# SCH_PHOENIX_-_PCB-2.net
KiCad netlist of a schematic drawn in EasyEDA
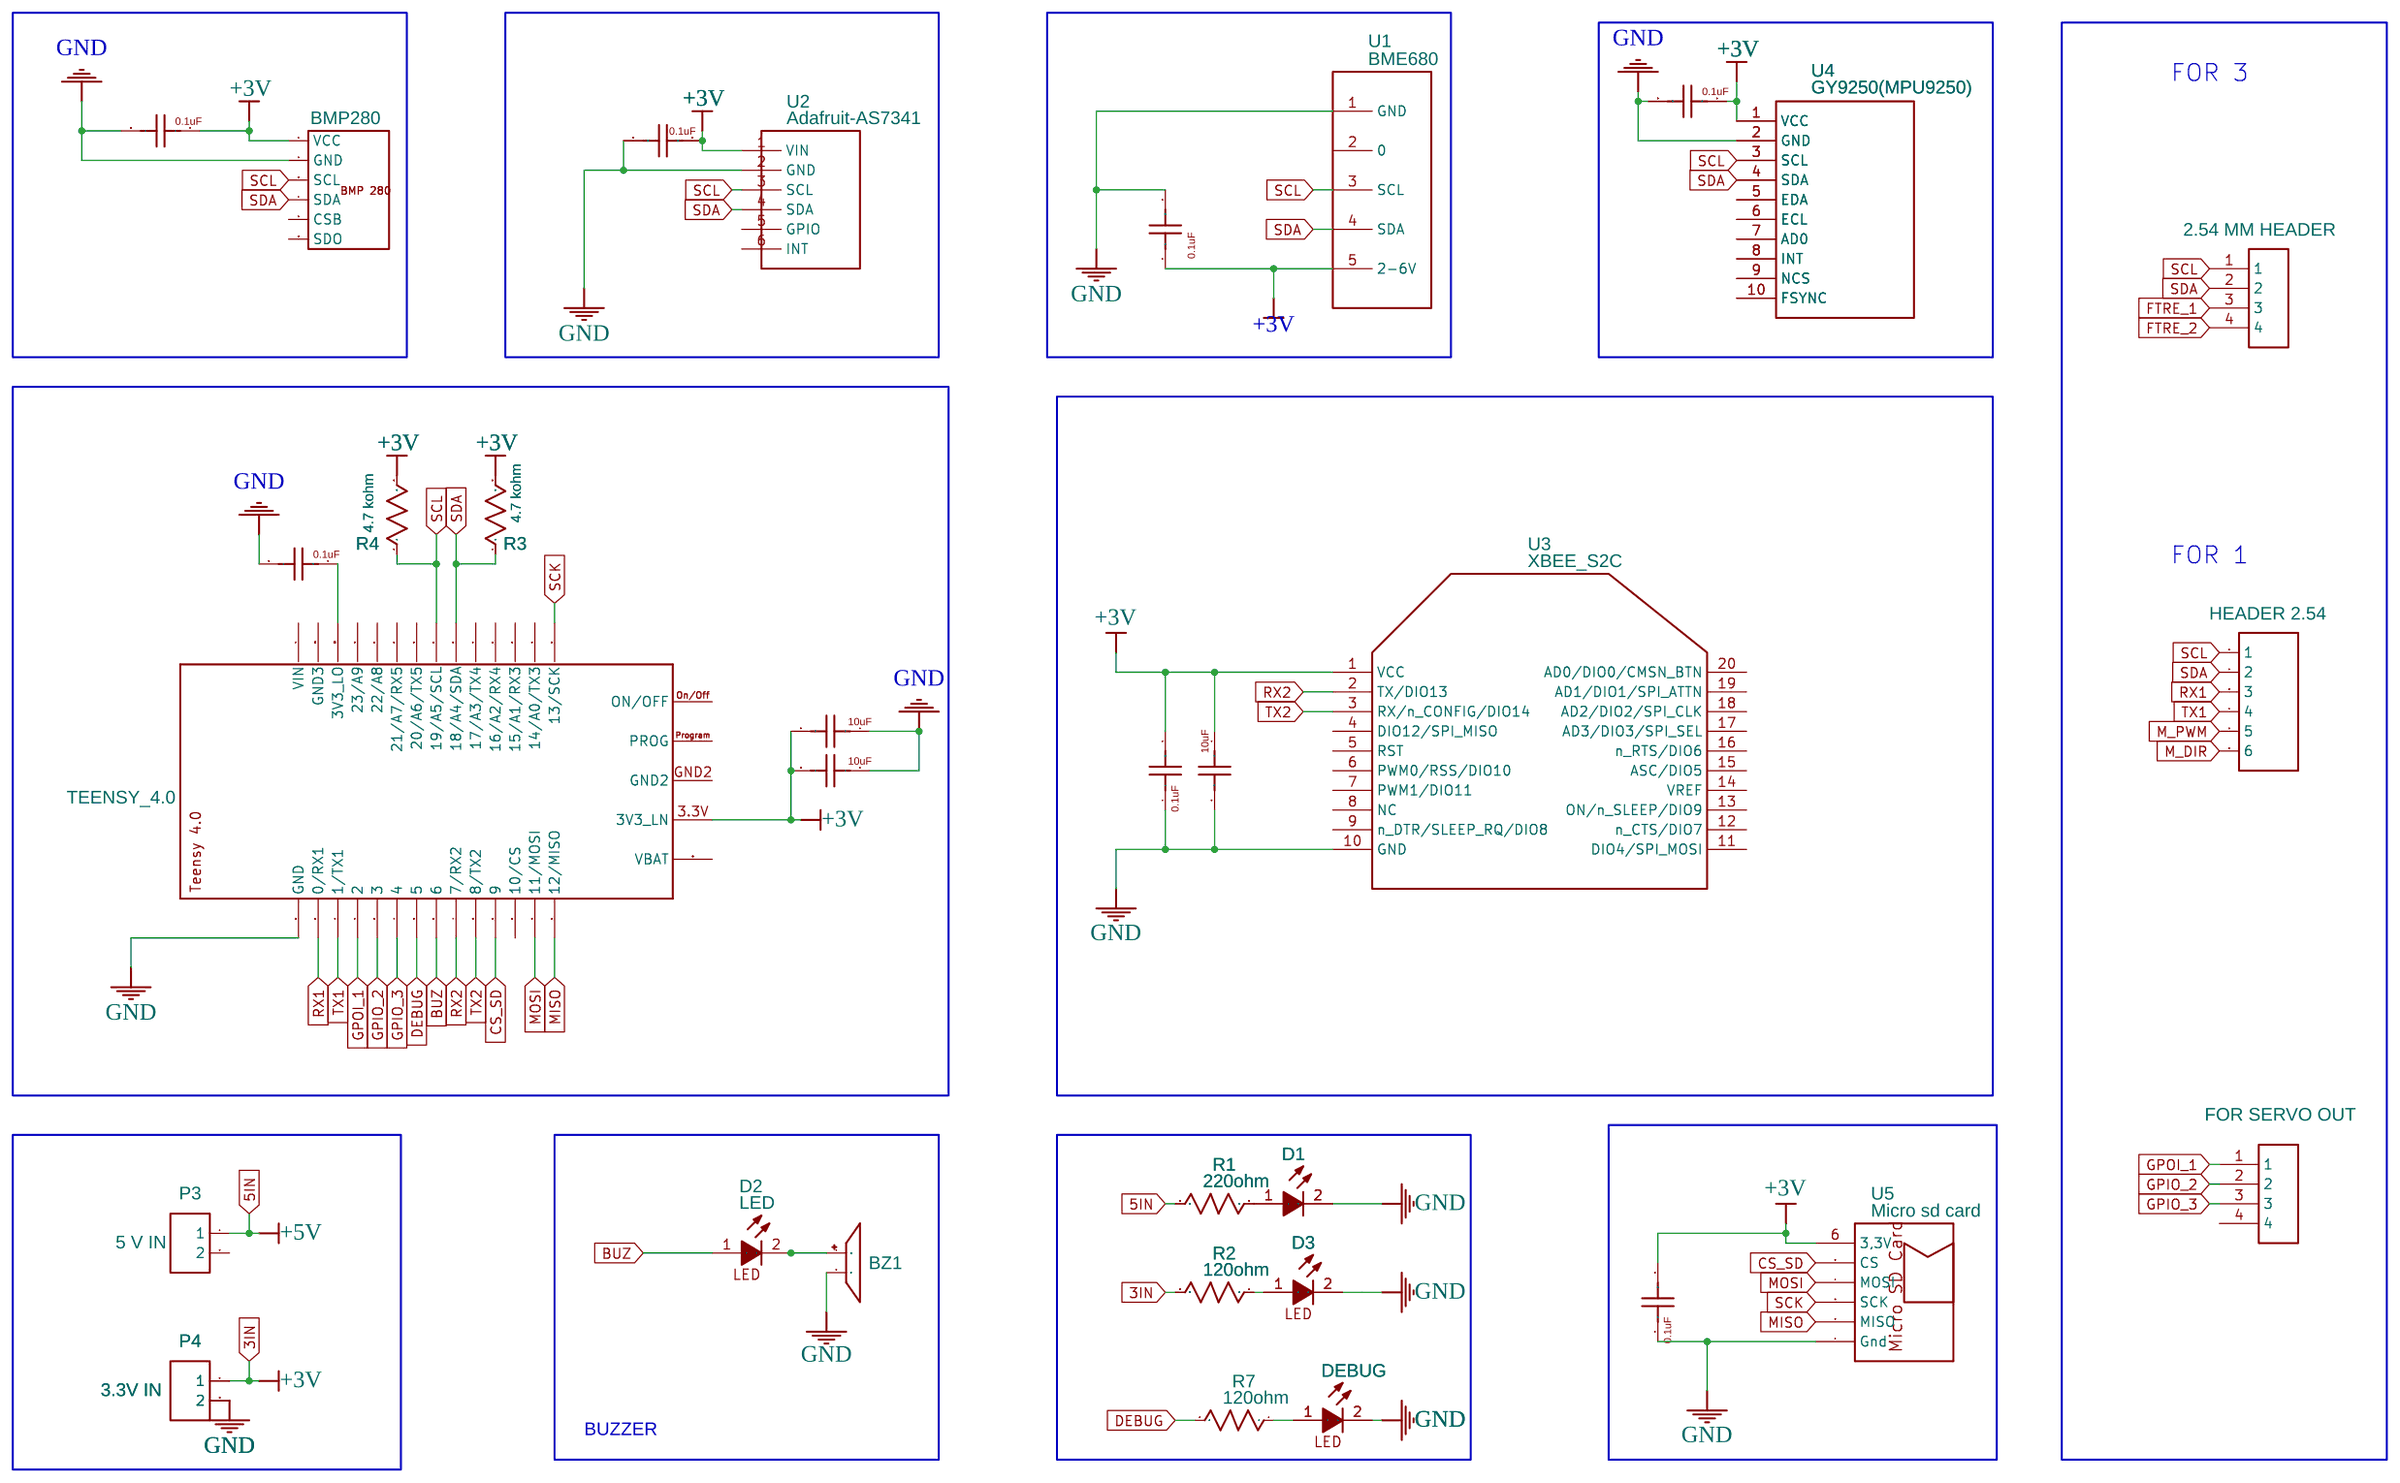
[diagram p0: schematic sheet]

(export (version "E")
  (design (tool "Eeschema 10.0.6"))
  (components
    (comp (ref "0") (value "TEENSY_4.0") (libsource (lib "") (part "TEENSY_4.0")))
    (comp (ref "BZ1") (value "Buzzer") (libsource (lib "") (part "Buzzer")))
    (comp (ref "C1") (value "22PF CERAMIC CAPACITOR") (libsource (lib "") (part "22PF CERAMIC CAPACITOR_1")))
    (comp (ref "C2") (value "22PF CERAMIC CAPACITOR") (libsource (lib "") (part "22PF CERAMIC CAPACITOR_1")))
    (comp (ref "C3") (value "22PF CERAMIC CAPACITOR") (libsource (lib "") (part "22PF CERAMIC CAPACITOR_6")))
    (comp (ref "C4") (value "22PF CERAMIC CAPACITOR") (libsource (lib "") (part "22PF CERAMIC CAPACITOR_3")))
    (comp (ref "C5") (value "22PF CERAMIC CAPACITOR") (libsource (lib "") (part "22PF CERAMIC CAPACITOR")))
    (comp (ref "C6") (value "22PF CERAMIC CAPACITOR") (libsource (lib "") (part "22PF CERAMIC CAPACITOR_3")))
    (comp (ref "C7") (value "22PF CERAMIC CAPACITOR") (libsource (lib "") (part "22PF CERAMIC CAPACITOR_4")))
    (comp (ref "C8") (value "22PF CERAMIC CAPACITOR") (libsource (lib "") (part "22PF CERAMIC CAPACITOR_5")))
    (comp (ref "C9") (value "22PF CERAMIC CAPACITOR") (libsource (lib "") (part "22PF CERAMIC CAPACITOR_2")))
    (comp (ref "C10") (value "22PF CERAMIC CAPACITOR") (libsource (lib "") (part "22PF CERAMIC CAPACITOR")))
    (comp (ref "D1")
      (value "LED")
      (fields (field (name "Manufacturer Part") "5600") (field (name "Manufacturer") "VccLite"))
      (libsource (lib "") (part "LED_1"))
    )
    (comp (ref "D2")
      (value "LED")
      (fields (field (name "Manufacturer Part") "5600") (field (name "Manufacturer") "VccLite"))
      (libsource (lib "") (part "LED"))
    )
    (comp (ref "D3")
      (value "LED")
      (fields (field (name "Manufacturer Part") "5600") (field (name "Manufacturer") "VccLite"))
      (libsource (lib "") (part "LED"))
    )
    (comp (ref "DEBUG")
      (value "LED")
      (fields (field (name "Manufacturer Part") "5600") (field (name "Manufacturer") "VccLite"))
      (libsource (lib "") (part "LED_2"))
    )
    (comp (ref "H1")
      (value "2.54 MM HEADER")
      (fields (field (name "Manufacturer Part") "2211S-04G") (field (name "Manufacturer") "MULTICOMP PRO"))
      (libsource (lib "") (part "B2B 2.54 MM HEADER"))
    )
    (comp (ref "H2")
      (value "FOR SERVO OUT")
      (fields (field (name "Manufacturer Part") "2211S-04G") (field (name "Manufacturer") "MULTICOMP PRO"))
      (libsource (lib "") (part "B2B 2.54 MM HEADER"))
    )
    (comp (ref "J1")
      (value "HEADER 2.54")
      (fields (field (name "Manufacturer Part") "2.54mm 1*20PHeader"))
      (libsource (lib "") (part "HEADER-MALE-2.54_1X6"))
    )
    (comp (ref "MOD1") (value "BMP280") (libsource (lib "") (part "BMP280")))
    (comp (ref "P3") (value "5 V IN") (libsource (lib "") (part "CONN-TH_2P-P5.00")))
    (comp (ref "P4") (value "3.3V IN") (libsource (lib "") (part "CONN-TH_2P-P5.00")))
    (comp (ref "R1") (value "220ohm") (libsource (lib "") (part "R_0603_US_1")))
    (comp (ref "R2") (value "120ohm") (libsource (lib "") (part "R_0603_US_1")))
    (comp (ref "R3") (value "4.7 kohm") (libsource (lib "") (part "R_0603_US")))
    (comp (ref "R4") (value "4.7 kohm") (libsource (lib "") (part "R_0603_US")))
    (comp (ref "R7") (value "120ohm") (libsource (lib "") (part "R_0603_US_1")))
    (comp (ref "U1") (value "BME680") (libsource (lib "") (part "BME680")))
    (comp (ref "U2") (value "Adafruit-AS7341") (libsource (lib "") (part "Adafruit-AS7341")))
    (comp (ref "U3")
      (value "XBEE_S2C")
      (fields
        (field (name "Manufacturer Part") "XBP24CZ7PITB003")
        (field (name "Manufacturer") "Digi International")
      )
      (libsource (lib "") (part "XBEE_S2C"))
    )
    (comp (ref "U4") (value "GY9250(MPU9250)") (libsource (lib "") (part "GY9250(MPU9250)")))
    (comp (ref "U5")
      (value "Micro sd card")
      (fields (field (name "Manufacturer Part") "Micro sd card module"))
      (libsource (lib "") (part "Micro sd card module"))
    )
  )
  (nets
    (net (code "1") (name "3IN") (class "Default")
      (node (ref "0") (pin "3.3V") (pinfunction "3V3_LN_3.3V") (pintype "bidirectional"))
      (node (ref "C1") (pin "2") (pinfunction "2_2") (pintype "unspecified"))
      (node (ref "C10") (pin "2") (pinfunction "2_2") (pintype "unspecified"))
      (node (ref "C2") (pin "2") (pinfunction "2_2") (pintype "unspecified"))
      (node (ref "C3") (pin "1") (pinfunction "1_1") (pintype "unspecified"))
      (node (ref "C5") (pin "2") (pinfunction "2_2") (pintype "unspecified"))
      (node (ref "C6") (pin "1") (pinfunction "1_1") (pintype "unspecified"))
      (node (ref "C7") (pin "1") (pinfunction "1_1") (pintype "unspecified"))
      (node (ref "C8") (pin "1") (pinfunction "1_1") (pintype "unspecified"))
      (node (ref "C9") (pin "1") (pinfunction "1_1") (pintype "unspecified"))
      (node (ref "MOD1") (pin "1") (pinfunction "VCC_1") (pintype "unspecified"))
      (node (ref "P4") (pin "1") (pinfunction "1_1") (pintype "unspecified"))
      (node (ref "R2") (pin "2") (pinfunction "2_2") (pintype "unspecified"))
      (node (ref "R3") (pin "2") (pinfunction "2_2") (pintype "unspecified"))
      (node (ref "R4") (pin "2") (pinfunction "2_2") (pintype "unspecified"))
      (node (ref "U1") (pin "5") (pinfunction "2-6V_5") (pintype "passive"))
      (node (ref "U2") (pin "1") (pinfunction "VIN_1") (pintype "unspecified"))
      (node (ref "U3") (pin "1") (pinfunction "VCC_1") (pintype "passive"))
      (node (ref "U4") (pin "1") (pinfunction "VCC_1") (pintype "unspecified"))
      (node (ref "U5") (pin "6") (pinfunction "3,3V_6") (pintype "unspecified"))
    )
    (net (code "2") (name "5IN") (class "Default")
      (node (ref "P3") (pin "1") (pinfunction "1_1") (pintype "unspecified"))
      (node (ref "R1") (pin "2") (pinfunction "2_2") (pintype "unspecified"))
    )
    (net (code "3") (name "BUZ") (class "Default")
      (node (ref "0") (pin "6") (pinfunction "6_6") (pintype "bidirectional"))
      (node (ref "D2") (pin "1") (pinfunction "A_1") (pintype "unspecified"))
    )
    (net (code "4") (name "CS_SD") (class "Default")
      (node (ref "0") (pin "9") (pinfunction "9_9") (pintype "bidirectional"))
      (node (ref "U5") (pin "5") (pinfunction "CS_5") (pintype "unspecified"))
    )
    (net (code "5") (name "DEBUG") (class "Default")
      (node (ref "0") (pin "5") (pinfunction "5_5") (pintype "bidirectional"))
      (node (ref "R7") (pin "2") (pinfunction "2_2") (pintype "unspecified"))
    )
    (net (code "6") (name "FTRE_1") (class "Default")
      (node (ref "H1") (pin "3") (pinfunction "3_3") (pintype "unspecified"))
    )
    (net (code "7") (name "FTRE_2") (class "Default")
      (node (ref "H1") (pin "4") (pinfunction "4_4") (pintype "unspecified"))
    )
    (net (code "8") (name "GND") (class "Default")
      (node (ref "0") (pin "GND1") (pinfunction "GND_GND1") (pintype "bidirectional"))
      (node (ref "BZ1") (pin "2") (pinfunction "2_2") (pintype "unspecified"))
      (node (ref "C1") (pin "1") (pinfunction "1_1") (pintype "unspecified"))
      (node (ref "C10") (pin "1") (pinfunction "1_1") (pintype "unspecified"))
      (node (ref "C2") (pin "1") (pinfunction "1_1") (pintype "unspecified"))
      (node (ref "C3") (pin "2") (pinfunction "2_2") (pintype "unspecified"))
      (node (ref "C4") (pin "2") (pinfunction "2_2") (pintype "unspecified"))
      (node (ref "C5") (pin "1") (pinfunction "1_1") (pintype "unspecified"))
      (node (ref "C6") (pin "2") (pinfunction "2_2") (pintype "unspecified"))
      (node (ref "C7") (pin "2") (pinfunction "2_2") (pintype "unspecified"))
      (node (ref "C8") (pin "2") (pinfunction "2_2") (pintype "unspecified"))
      (node (ref "C9") (pin "2") (pinfunction "2_2") (pintype "unspecified"))
      (node (ref "D1") (pin "2") (pinfunction "K_2") (pintype "unspecified"))
      (node (ref "D3") (pin "2") (pinfunction "K_2") (pintype "unspecified"))
      (node (ref "DEBUG") (pin "2") (pinfunction "K_2") (pintype "unspecified"))
      (node (ref "MOD1") (pin "2") (pinfunction "GND_2") (pintype "unspecified"))
      (node (ref "P4") (pin "2") (pinfunction "2_2") (pintype "unspecified"))
      (node (ref "U1") (pin "1") (pinfunction "GND_1") (pintype "passive"))
      (node (ref "U2") (pin "2") (pinfunction "GND_2") (pintype "unspecified"))
      (node (ref "U3") (pin "10") (pinfunction "GND_10") (pintype "passive"))
      (node (ref "U4") (pin "2") (pinfunction "GND_2") (pintype "unspecified"))
      (node (ref "U5") (pin "1") (pinfunction "Gnd_1") (pintype "unspecified"))
    )
    (net (code "9") (name "GPIO_2") (class "Default")
      (node (ref "0") (pin "3") (pinfunction "3_3") (pintype "bidirectional"))
      (node (ref "H2") (pin "2") (pinfunction "2_2") (pintype "unspecified"))
    )
    (net (code "10") (name "GPIO_3") (class "Default")
      (node (ref "0") (pin "4") (pinfunction "4_4") (pintype "bidirectional"))
      (node (ref "H2") (pin "3") (pinfunction "3_3") (pintype "unspecified"))
    )
    (net (code "11") (name "GPOI_1") (class "Default")
      (node (ref "0") (pin "2") (pinfunction "2_2") (pintype "bidirectional"))
      (node (ref "H2") (pin "1") (pinfunction "1_1") (pintype "unspecified"))
    )
    (net (code "12") (name "MISO") (class "Default")
      (node (ref "0") (pin "12") (pinfunction "12/MISO_12") (pintype "bidirectional"))
      (node (ref "U5") (pin "2") (pinfunction "MISO_2") (pintype "unspecified"))
    )
    (net (code "13") (name "MOSI") (class "Default")
      (node (ref "0") (pin "11") (pinfunction "11/MOSI_11") (pintype "bidirectional"))
      (node (ref "U5") (pin "4") (pinfunction "MOSI_4") (pintype "unspecified"))
    )
    (net (code "14") (name "M_DIR") (class "Default")
      (node (ref "J1") (pin "6") (pinfunction "6_6") (pintype "input"))
    )
    (net (code "15") (name "M_PWM") (class "Default")
      (node (ref "J1") (pin "5") (pinfunction "5_5") (pintype "input"))
    )
    (net (code "16") (name "Net-(0-3V3_LO)") (class "Default")
      (node (ref "0") (pin "3.3V/250") (pinfunction "3V3_LO_3.3V/250") (pintype "bidirectional"))
      (node (ref "C4") (pin "1") (pinfunction "1_1") (pintype "unspecified"))
    )
    (net (code "17") (name "Net-(BZ1-Buzzer)") (class "Default")
      (node (ref "BZ1") (pin "1") (pinfunction "Buzzer_1") (pintype "unspecified"))
      (node (ref "D2") (pin "2") (pinfunction "K_2") (pintype "unspecified"))
    )
    (net (code "18") (name "Net-(D1-A)") (class "Default")
      (node (ref "D1") (pin "1") (pinfunction "A_1") (pintype "unspecified"))
      (node (ref "R1") (pin "1") (pinfunction "1_1") (pintype "unspecified"))
    )
    (net (code "19") (name "Net-(D3-A)") (class "Default")
      (node (ref "D3") (pin "1") (pinfunction "A_1") (pintype "unspecified"))
      (node (ref "R2") (pin "1") (pinfunction "1_1") (pintype "unspecified"))
    )
    (net (code "20") (name "Net-(DEBUG-A)") (class "Default")
      (node (ref "DEBUG") (pin "1") (pinfunction "A_1") (pintype "unspecified"))
      (node (ref "R7") (pin "1") (pinfunction "1_1") (pintype "unspecified"))
    )
    (net (code "21") (name "RX1") (class "Default")
      (node (ref "0") (pin "0") (pinfunction "0/RX1_0") (pintype "bidirectional"))
      (node (ref "J1") (pin "3") (pinfunction "3_3") (pintype "input"))
    )
    (net (code "22") (name "RX2") (class "Default")
      (node (ref "0") (pin "7") (pinfunction "7/RX2_7") (pintype "bidirectional"))
      (node (ref "U3") (pin "2") (pinfunction "TX/DIO13_2") (pintype "output"))
    )
    (net (code "23") (name "SCK") (class "Default")
      (node (ref "0") (pin "13") (pinfunction "13/SCK_13") (pintype "bidirectional"))
      (node (ref "U5") (pin "3") (pinfunction "SCK_3") (pintype "unspecified"))
    )
    (net (code "24") (name "SCL") (class "Default")
      (node (ref "0") (pin "19") (pinfunction "19/A5/SCL_19") (pintype "bidirectional"))
      (node (ref "H1") (pin "1") (pinfunction "1_1") (pintype "unspecified"))
      (node (ref "J1") (pin "1") (pinfunction "1_1") (pintype "input"))
      (node (ref "MOD1") (pin "3") (pinfunction "SCL_3") (pintype "unspecified"))
      (node (ref "R4") (pin "1") (pinfunction "1_1") (pintype "unspecified"))
      (node (ref "U1") (pin "3") (pinfunction "SCL_3") (pintype "bidirectional"))
      (node (ref "U2") (pin "3") (pinfunction "SCL_3") (pintype "unspecified"))
      (node (ref "U4") (pin "3") (pinfunction "SCL_3") (pintype "unspecified"))
    )
    (net (code "25") (name "SDA") (class "Default")
      (node (ref "0") (pin "18") (pinfunction "18/A4/SDA_18") (pintype "bidirectional"))
      (node (ref "H1") (pin "2") (pinfunction "2_2") (pintype "unspecified"))
      (node (ref "J1") (pin "2") (pinfunction "2_2") (pintype "input"))
      (node (ref "MOD1") (pin "4") (pinfunction "SDA_4") (pintype "unspecified"))
      (node (ref "R3") (pin "1") (pinfunction "1_1") (pintype "unspecified"))
      (node (ref "U1") (pin "4") (pinfunction "SDA_4") (pintype "bidirectional"))
      (node (ref "U2") (pin "4") (pinfunction "SDA_4") (pintype "unspecified"))
      (node (ref "U4") (pin "4") (pinfunction "SDA_4") (pintype "unspecified"))
    )
    (net (code "26") (name "TX1") (class "Default")
      (node (ref "0") (pin "1") (pinfunction "1/TX1_1") (pintype "bidirectional"))
      (node (ref "J1") (pin "4") (pinfunction "4_4") (pintype "input"))
    )
    (net (code "27") (name "TX2") (class "Default")
      (node (ref "0") (pin "8") (pinfunction "8/TX2_8") (pintype "bidirectional"))
      (node (ref "U3") (pin "3") (pinfunction "RX/n_CONFIG/DIO14_3") (pintype "input"))
    )
    (net (code "28") (name "unconnected-(0-10{slash}CS-Pad10)") (class "Default")
      (node (ref "0") (pin "10") (pinfunction "10/CS_10") (pintype "bidirectional"))
    )
    (net (code "29") (name "unconnected-(0-14{slash}A0{slash}TX3-Pad14)") (class "Default")
      (node (ref "0") (pin "14") (pinfunction "14/A0/TX3_14") (pintype "bidirectional"))
    )
    (net (code "30") (name "unconnected-(0-15{slash}A1{slash}RX3-Pad15)") (class "Default")
      (node (ref "0") (pin "15") (pinfunction "15/A1/RX3_15") (pintype "bidirectional"))
    )
    (net (code "31") (name "unconnected-(0-16{slash}A2{slash}RX4-Pad16)") (class "Default")
      (node (ref "0") (pin "16") (pinfunction "16/A2/RX4_16") (pintype "bidirectional"))
    )
    (net (code "32") (name "unconnected-(0-17{slash}A3{slash}TX4-Pad17)") (class "Default")
      (node (ref "0") (pin "17") (pinfunction "17/A3/TX4_17") (pintype "bidirectional"))
    )
    (net (code "33") (name "unconnected-(0-20{slash}A6{slash}TX5-Pad20)") (class "Default")
      (node (ref "0") (pin "20") (pinfunction "20/A6/TX5_20") (pintype "bidirectional"))
    )
    (net (code "34") (name "unconnected-(0-21{slash}A7{slash}RX5-Pad21)") (class "Default")
      (node (ref "0") (pin "21") (pinfunction "21/A7/RX5_21") (pintype "bidirectional"))
    )
    (net (code "35") (name "unconnected-(0-22{slash}A8-Pad22)") (class "Default")
      (node (ref "0") (pin "22") (pinfunction "22/A8_22") (pintype "bidirectional"))
    )
    (net (code "36") (name "unconnected-(0-23{slash}A9-Pad23)") (class "Default")
      (node (ref "0") (pin "23") (pinfunction "23/A9_23") (pintype "bidirectional"))
    )
    (net (code "37") (name "unconnected-(0-ON{slash}OFF-PadOn{slash}Off)") (class "Default")
      (node (ref "0") (pin "On/Off") (pinfunction "ON/OFF_On/Off") (pintype "bidirectional"))
    )
    (net (code "38") (name "unconnected-(0-PROG-PadProgram)") (class "Default")
      (node (ref "0") (pin "Program") (pinfunction "PROG_Program") (pintype "bidirectional"))
    )
    (net (code "39") (name "unconnected-(0-PadGND2)") (class "Default")
      (node (ref "0") (pin "GND2") (pinfunction "GND2_GND2") (pintype "bidirectional"))
    )
    (net (code "40") (name "unconnected-(0-PadGND3)") (class "Default")
      (node (ref "0") (pin "GND3") (pinfunction "GND3_GND3") (pintype "bidirectional"))
    )
    (net (code "41") (name "unconnected-(0-PadVIN)") (class "Default")
      (node (ref "0") (pin "VIN") (pinfunction "VIN_VIN") (pintype "bidirectional"))
    )
    (net (code "42") (name "unconnected-(0-VBAT-PadVBat)") (class "Default")
      (node (ref "0") (pin "VBat") (pinfunction "VBAT_VBat") (pintype "bidirectional"))
    )
    (net (code "43") (name "unconnected-(H2-Pad4)") (class "Default")
      (node (ref "H2") (pin "4") (pinfunction "4_4") (pintype "unspecified"))
    )
    (net (code "44") (name "unconnected-(MOD1-CSB-Pad5)") (class "Default")
      (node (ref "MOD1") (pin "5") (pinfunction "CSB_5") (pintype "unspecified"))
    )
    (net (code "45") (name "unconnected-(MOD1-SDO-Pad6)") (class "Default")
      (node (ref "MOD1") (pin "6") (pinfunction "SDO_6") (pintype "unspecified"))
    )
    (net (code "46") (name "unconnected-(P3-Pad2)") (class "Default")
      (node (ref "P3") (pin "2") (pinfunction "2_2") (pintype "unspecified"))
    )
    (net (code "47") (name "unconnected-(U1-0-Pad2)") (class "Default")
      (node (ref "U1") (pin "2") (pinfunction "0_2") (pintype "unspecified"))
    )
    (net (code "48") (name "unconnected-(U2-GPIO-Pad5)") (class "Default")
      (node (ref "U2") (pin "5") (pinfunction "GPIO_5") (pintype "unspecified"))
    )
    (net (code "49") (name "unconnected-(U2-INT-Pad6)") (class "Default")
      (node (ref "U2") (pin "6") (pinfunction "INT_6") (pintype "unspecified"))
    )
    (net (code "50") (name "unconnected-(U3-AD0{slash}DIO0{slash}CMSN_BTN-Pad20)") (class "Default")
      (node (ref "U3") (pin "20") (pinfunction "AD0/DIO0/CMSN_BTN_20") (pintype "input"))
    )
    (net (code "51") (name "unconnected-(U3-AD1{slash}DIO1{slash}SPI_ATTN-Pad19)") (class "Default")
      (node (ref "U3") (pin "19") (pinfunction "AD1/DIO1/SPI_ATTN_19") (pintype "bidirectional"))
    )
    (net (code "52") (name "unconnected-(U3-AD2{slash}DIO2{slash}SPI_CLK-Pad18)") (class "Default")
      (node (ref "U3") (pin "18") (pinfunction "AD2/DIO2/SPI_CLK_18") (pintype "bidirectional"))
    )
    (net (code "53") (name "unconnected-(U3-AD3{slash}DIO3{slash}SPI_SEL-Pad17)") (class "Default")
      (node (ref "U3") (pin "17") (pinfunction "AD3/DIO3/SPI_SEL_17") (pintype "bidirectional"))
    )
    (net (code "54") (name "unconnected-(U3-ASC{slash}DIO5-Pad15)") (class "Default")
      (node (ref "U3") (pin "15") (pinfunction "ASC/DIO5_15") (pintype "input"))
    )
    (net (code "55") (name "unconnected-(U3-DIO4{slash}SPI_MOSI-Pad11)") (class "Default")
      (node (ref "U3") (pin "11") (pinfunction "DIO4/SPI_MOSI_11") (pintype "input"))
    )
    (net (code "56") (name "unconnected-(U3-DIO12{slash}SPI_MISO-Pad4)") (class "Default")
      (node (ref "U3") (pin "4") (pinfunction "DIO12/SPI_MISO_4") (pintype "bidirectional"))
    )
    (net (code "57") (name "unconnected-(U3-NC-Pad8)") (class "Default")
      (node (ref "U3") (pin "8") (pinfunction "NC_8") (pintype "input"))
    )
    (net (code "58") (name "unconnected-(U3-ON{slash}n_SLEEP{slash}DIO9-Pad13)") (class "Default")
      (node (ref "U3") (pin "13") (pinfunction "ON/n_SLEEP/DIO9_13") (pintype "bidirectional"))
    )
    (net (code "59") (name "unconnected-(U3-PWM0{slash}RSS{slash}DIO10-Pad6)") (class "Default")
      (node (ref "U3") (pin "6") (pinfunction "PWM0/RSS/DIO10_6") (pintype "input"))
    )
    (net (code "60") (name "unconnected-(U3-PWM1{slash}DIO11-Pad7)") (class "Default")
      (node (ref "U3") (pin "7") (pinfunction "PWM1/DIO11_7") (pintype "input"))
    )
    (net (code "61") (name "unconnected-(U3-RST-Pad5)") (class "Default")
      (node (ref "U3") (pin "5") (pinfunction "RST_5") (pintype "input"))
    )
    (net (code "62") (name "unconnected-(U3-VREF-Pad14)") (class "Default")
      (node (ref "U3") (pin "14") (pinfunction "VREF_14") (pintype "input"))
    )
    (net (code "63") (name "unconnected-(U3-n_CTS{slash}DIO7-Pad12)") (class "Default")
      (node (ref "U3") (pin "12") (pinfunction "n_CTS/DIO7_12") (pintype "unspecified"))
    )
    (net (code "64") (name "unconnected-(U3-n_DTR{slash}SLEEP_RQ{slash}DIO8-Pad9)") (class "Default")
      (node (ref "U3") (pin "9") (pinfunction "n_DTR/SLEEP_RQ/DIO8_9") (pintype "bidirectional"))
    )
    (net (code "65") (name "unconnected-(U3-n_RTS{slash}DIO6-Pad16)") (class "Default")
      (node (ref "U3") (pin "16") (pinfunction "n_RTS/DIO6_16") (pintype "bidirectional"))
    )
    (net (code "66") (name "unconnected-(U4-AD0-Pad7)") (class "Default")
      (node (ref "U4") (pin "7") (pinfunction "AD0_7") (pintype "unspecified"))
    )
    (net (code "67") (name "unconnected-(U4-ECL-Pad6)") (class "Default")
      (node (ref "U4") (pin "6") (pinfunction "ECL_6") (pintype "unspecified"))
    )
    (net (code "68") (name "unconnected-(U4-EDA-Pad5)") (class "Default")
      (node (ref "U4") (pin "5") (pinfunction "EDA_5") (pintype "unspecified"))
    )
    (net (code "69") (name "unconnected-(U4-FSYNC-Pad10)") (class "Default")
      (node (ref "U4") (pin "10") (pinfunction "FSYNC_10") (pintype "unspecified"))
    )
    (net (code "70") (name "unconnected-(U4-INT-Pad8)") (class "Default")
      (node (ref "U4") (pin "8") (pinfunction "INT_8") (pintype "unspecified"))
    )
    (net (code "71") (name "unconnected-(U4-NCS-Pad9)") (class "Default")
      (node (ref "U4") (pin "9") (pinfunction "NCS_9") (pintype "unspecified"))
    )
  )
)
